# MainBoard.net
KiCad netlist of a schematic drawn in EAGLE
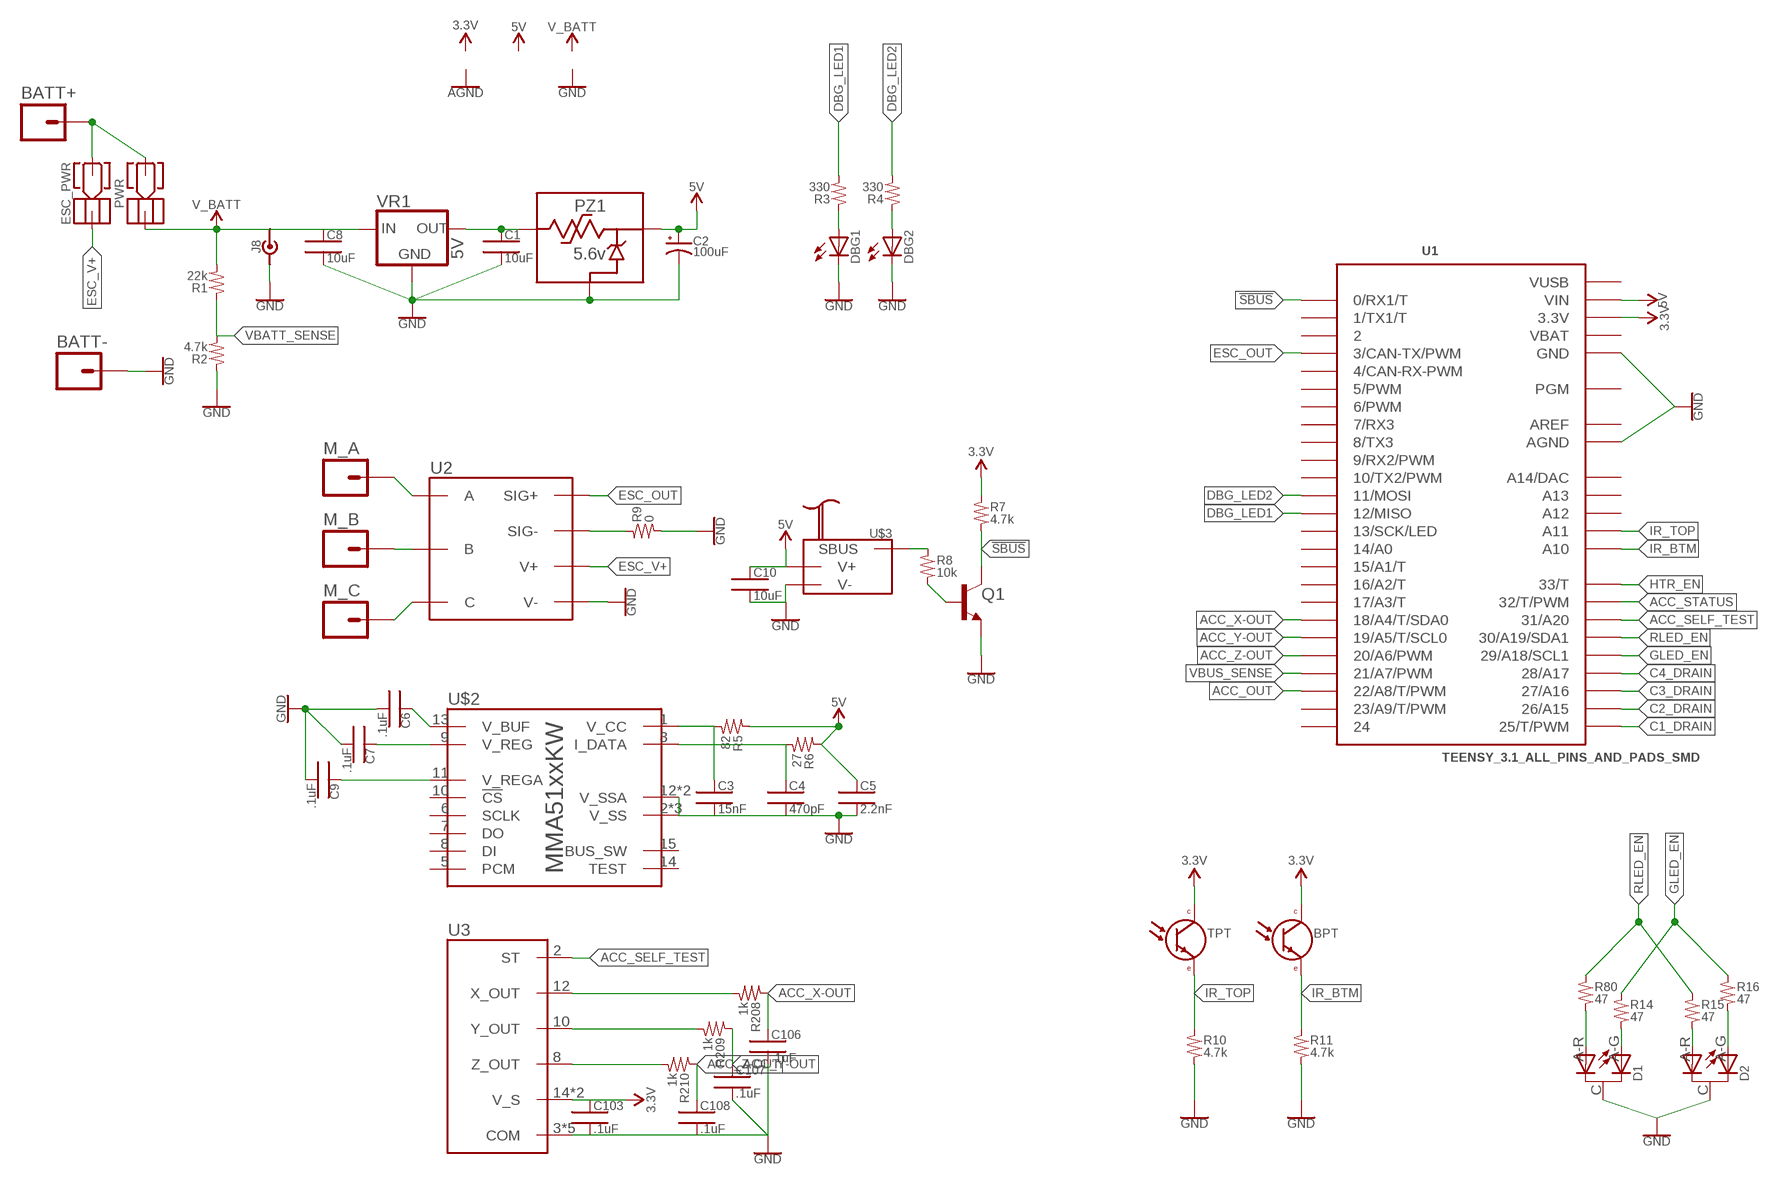
[diagram p0: schematic, sheet 1]

(export (version "E")
  (design (tool "Eeschema 10.0.6"))
  (components
    (comp (ref "BATT+")
      (value "14AWG_PTH")
      (footprint "eagle-import:14AWG_PTH")
      (libsource (lib "eagle-import") (part "14AWG_PTH"))
    )
    (comp (ref "BATT-")
      (value "14AWG_PTH")
      (footprint "eagle-import:14AWG_PTH")
      (libsource (lib "eagle-import") (part "14AWG_PTH"))
    )
    (comp (ref "BPT")
      (value "PHOTOTRANSISTOR_OPXXX-H")
      (footprint "eagle-import:OP550+_HORIZ")
      (libsource (lib "eagle-import") (part "PHOTOTRANSISTOR_OPXXX-H"))
    )
    (comp (ref "C1")
      (value "10uF")
      (footprint "eagle-import:0805")
      (libsource (lib "eagle-import") (part "CAP_SMD_0805"))
    )
    (comp (ref "C2")
      (value "100uF")
      (footprint "eagle-import:2917_D-CASE")
      (libsource (lib "eagle-import") (part "CAP_POL_SMD"))
    )
    (comp (ref "C3")
      (value "15nF")
      (footprint "eagle-import:0805")
      (libsource (lib "eagle-import") (part "CAP_SMD_0805"))
    )
    (comp (ref "C4")
      (value "470pF")
      (footprint "eagle-import:0805")
      (libsource (lib "eagle-import") (part "CAP_SMD_0805"))
    )
    (comp (ref "C5")
      (value "2.2nF")
      (footprint "eagle-import:0805")
      (libsource (lib "eagle-import") (part "CAP_SMD_0805"))
    )
    (comp (ref "C6")
      (value ".1uF")
      (footprint "eagle-import:0805")
      (libsource (lib "eagle-import") (part "CAP_SMD_0805"))
    )
    (comp (ref "C7")
      (value ".1uF")
      (footprint "eagle-import:0805")
      (libsource (lib "eagle-import") (part "CAP_SMD_0805"))
    )
    (comp (ref "C8")
      (value "10uF")
      (footprint "eagle-import:0805")
      (libsource (lib "eagle-import") (part "CAP_SMD_0805"))
    )
    (comp (ref "C9")
      (value ".1uF")
      (footprint "eagle-import:0805")
      (libsource (lib "eagle-import") (part "CAP_SMD_0805"))
    )
    (comp (ref "C10")
      (value "10uF")
      (footprint "eagle-import:0805")
      (libsource (lib "eagle-import") (part "CAP_SMD_0805"))
    )
    (comp (ref "C103")
      (value ".1uF")
      (footprint "eagle-import:0805")
      (libsource (lib "eagle-import") (part "CAP_SMD_0805"))
    )
    (comp (ref "C106")
      (value ".1uF")
      (footprint "eagle-import:0805")
      (libsource (lib "eagle-import") (part "CAP_SMD_0805"))
    )
    (comp (ref "C107")
      (value ".1uF")
      (footprint "eagle-import:0805")
      (libsource (lib "eagle-import") (part "CAP_SMD_0805"))
    )
    (comp (ref "C108")
      (value ".1uF")
      (footprint "eagle-import:0805")
      (libsource (lib "eagle-import") (part "CAP_SMD_0805"))
    )
    (comp (ref "D1")
      (value "TLVS5100")
      (footprint "eagle-import:TLSV5100")
      (libsource (lib "eagle-import") (part "TLVS5100"))
    )
    (comp (ref "D2")
      (value "TLVS5100")
      (footprint "eagle-import:TLSV5100")
      (libsource (lib "eagle-import") (part "TLVS5100"))
    )
    (comp (ref "DBG1")
      (value "LED1206")
      (footprint "eagle-import:LED-1206")
      (libsource (lib "eagle-import") (part "LED1206"))
    )
    (comp (ref "DBG2")
      (value "LED1206")
      (footprint "eagle-import:LED-1206")
      (libsource (lib "eagle-import") (part "LED1206"))
    )
    (comp (ref "ESC_PWR")
      (value "SCREW_SW_M3")
      (footprint "eagle-import:SCREW_SW_M3")
      (libsource (lib "eagle-import") (part "SCREW_SW_M3"))
    )
    (comp (ref "J8")
      (value "PJ-082BH")
      (footprint "eagle-import:PJ-082BH")
      (libsource (lib "eagle-import") (part "PJ-082BH"))
    )
    (comp (ref "M_A")
      (value "14AWG_PTH")
      (footprint "eagle-import:14AWG_PTH")
      (libsource (lib "eagle-import") (part "14AWG_PTH"))
    )
    (comp (ref "M_B")
      (value "14AWG_PTH")
      (footprint "eagle-import:14AWG_PTH")
      (libsource (lib "eagle-import") (part "14AWG_PTH"))
    )
    (comp (ref "M_C")
      (value "14AWG_PTH")
      (footprint "eagle-import:14AWG_PTH")
      (libsource (lib "eagle-import") (part "14AWG_PTH"))
    )
    (comp (ref "PWR")
      (value "SCREW_SW_M3")
      (footprint "eagle-import:SCREW_SW_M3")
      (libsource (lib "eagle-import") (part "SCREW_SW_M3"))
    )
    (comp (ref "PZ1")
      (value "5.6v")
      (footprint "eagle-import:POLYZEN_LS")
      (libsource (lib "eagle-import") (part "POLYZEN_LS"))
    )
    (comp (ref "Q1")
      (value "BJT_NPN")
      (footprint "eagle-import:SOT23-3")
      (libsource (lib "eagle-import") (part "BJT_NPN"))
    )
    (comp (ref "R1")
      (value "22k")
      (footprint "eagle-import:0805")
      (libsource (lib "eagle-import") (part "RES_SMD0805"))
    )
    (comp (ref "R2")
      (value "4.7k")
      (footprint "eagle-import:0805")
      (libsource (lib "eagle-import") (part "RES_SMD0805"))
    )
    (comp (ref "R3")
      (value "330")
      (footprint "eagle-import:0805")
      (libsource (lib "eagle-import") (part "RES_SMD0805"))
    )
    (comp (ref "R4")
      (value "330")
      (footprint "eagle-import:0805")
      (libsource (lib "eagle-import") (part "RES_SMD0805"))
    )
    (comp (ref "R5")
      (value "82")
      (footprint "eagle-import:0805")
      (libsource (lib "eagle-import") (part "RES_SMD0805"))
    )
    (comp (ref "R6")
      (value "27")
      (footprint "eagle-import:0805")
      (libsource (lib "eagle-import") (part "RES_SMD0805"))
    )
    (comp (ref "R7")
      (value "4.7k")
      (footprint "eagle-import:0805")
      (libsource (lib "eagle-import") (part "RES_SMD0805"))
    )
    (comp (ref "R8")
      (value "10k")
      (footprint "eagle-import:0805")
      (libsource (lib "eagle-import") (part "RES_SMD0805"))
    )
    (comp (ref "R9")
      (value "0")
      (footprint "eagle-import:0805")
      (libsource (lib "eagle-import") (part "RES_SMD0805"))
    )
    (comp (ref "R10")
      (value "4.7k")
      (footprint "eagle-import:0805")
      (libsource (lib "eagle-import") (part "RES_SMD0805"))
    )
    (comp (ref "R11")
      (value "4.7k")
      (footprint "eagle-import:0805")
      (libsource (lib "eagle-import") (part "RES_SMD0805"))
    )
    (comp (ref "R14")
      (value "47")
      (footprint "eagle-import:0805")
      (libsource (lib "eagle-import") (part "RES_SMD0805"))
    )
    (comp (ref "R15")
      (value "47")
      (footprint "eagle-import:0805")
      (libsource (lib "eagle-import") (part "RES_SMD0805"))
    )
    (comp (ref "R16")
      (value "47")
      (footprint "eagle-import:0805")
      (libsource (lib "eagle-import") (part "RES_SMD0805"))
    )
    (comp (ref "R80")
      (value "47")
      (footprint "eagle-import:0805")
      (libsource (lib "eagle-import") (part "RES_SMD0805"))
    )
    (comp (ref "R208")
      (value "1k")
      (footprint "eagle-import:0805")
      (libsource (lib "eagle-import") (part "RES_SMD0805"))
    )
    (comp (ref "R209")
      (value "1k")
      (footprint "eagle-import:0805")
      (libsource (lib "eagle-import") (part "RES_SMD0805"))
    )
    (comp (ref "R210")
      (value "1k")
      (footprint "eagle-import:0805")
      (libsource (lib "eagle-import") (part "RES_SMD0805"))
    )
    (comp (ref "TPT")
      (value "PHOTOTRANSISTOR_OPXXX-H")
      (footprint "eagle-import:OP550+_HORIZ")
      (libsource (lib "eagle-import") (part "PHOTOTRANSISTOR_OPXXX-H"))
    )
    (comp (ref "U$2")
      (value "MMA51XXKW")
      (footprint "eagle-import:QFN16")
      (libsource (lib "eagle-import") (part "MMA51XXKW"))
    )
    (comp (ref "U$3")
      (value "SBUS_RC_RX_FRSKY-XMPM")
      (footprint "eagle-import:FRSKY_XM_PLUS_MINI")
      (libsource (lib "eagle-import") (part "SBUS_RC_RX_FRSKY-XMPM"))
    )
    (comp (ref "U1")
      (value "TEENSY_3.1_ALL_PINS_AND_PADS_SMD")
      (footprint "eagle-import:TEENSY_3.1_SMD_ALLPINS")
      (libsource (lib "eagle-import") (part "TEENSY_3.1_ALL_PINS_AND_PADS_SMD"))
    )
    (comp (ref "U2")
      (value "ZTW_30A_BLDCESC")
      (footprint "eagle-import:ZTW_SPIDER_30A_HV_OPTO_ESC")
      (libsource (lib "eagle-import") (part "ZTW_30A_BLDCESC"))
    )
    (comp (ref "U3")
      (value "ADXL326_QFN16")
      (footprint "eagle-import:QFN16")
      (libsource (lib "eagle-import") (part "ADXL326_QFN16"))
    )
    (comp (ref "VR1")
      (value "5V")
      (footprint "eagle-import:TSR_2-XXXX")
      (libsource (lib "eagle-import") (part "TSR_2-XXXX"))
    )
  )
  (nets
    (net (code "1") (name "/AREF") (class "Default")
      (node (ref "U1") (pin "AREF") (pinfunction "AREF_AREF") (pintype "power_in"))
    )
    (net (code "2") (name "/VBAT") (class "Default")
      (node (ref "U1") (pin "VBAT") (pinfunction "VBAT_VBAT") (pintype "power_in"))
    )
    (net (code "3") (name "/VUSB") (class "Default")
      (node (ref "U1") (pin "VUSB") (pinfunction "VUSB_VUSB") (pintype "power_in"))
    )
    (net (code "4") (name "/~{SBUS}") (class "Default")
      (node (ref "Q1") (pin "3") (pinfunction "C_3") (pintype "passive"))
      (node (ref "R7") (pin "2") (pinfunction "2_2") (pintype "passive"))
      (node (ref "U1") (pin "0") (pinfunction "0/RX1/T_0") (pintype "bidirectional"))
    )
    (net (code "5") (name "3.3V") (class "Default")
      (node (ref "BPT") (pin "C") (pinfunction "C_C") (pintype "bidirectional"))
      (node (ref "C103") (pin "1") (pinfunction "1_1") (pintype "passive"))
      (node (ref "R7") (pin "1") (pinfunction "1_1") (pintype "passive"))
      (node (ref "TPT") (pin "C") (pinfunction "C_C") (pintype "bidirectional"))
      (node (ref "U1") (pin "3.3V") (pinfunction "3.3V_3.3V") (pintype "power_in"))
      (node (ref "U1") (pin "3.3V1") (pinfunction "3.3V_3.3V1") (pintype "power_in"))
      (node (ref "U1") (pin "3.3V2") (pinfunction "3.3V_3.3V2") (pintype "power_in"))
      (node (ref "U3") (pin "14") (pinfunction "V_S_14") (pintype "bidirectional"))
      (node (ref "U3") (pin "15") (pinfunction "V_S_15") (pintype "bidirectional"))
    )
    (net (code "6") (name "5V") (class "Default")
      (node (ref "C10") (pin "1") (pinfunction "1_1") (pintype "passive"))
      (node (ref "C2") (pin "A+") (pinfunction "+_A+") (pintype "passive"))
      (node (ref "C5") (pin "1") (pinfunction "1_1") (pintype "passive"))
      (node (ref "PZ1") (pin "VOUT") (pinfunction "V_OUT_VOUT") (pintype "bidirectional"))
      (node (ref "R5") (pin "1") (pinfunction "1_1") (pintype "passive"))
      (node (ref "R6") (pin "1") (pinfunction "1_1") (pintype "passive"))
      (node (ref "U$3") (pin "5V") (pinfunction "V+_5V") (pintype "bidirectional"))
      (node (ref "U1") (pin "VIN") (pinfunction "VIN_VIN") (pintype "power_in"))
    )
    (net (code "7") (name "ACC_OUT") (class "Default")
      (node (ref "U1") (pin "22/A8") (pinfunction "22/A8/T/PWM_22/A8") (pintype "bidirectional"))
    )
    (net (code "8") (name "ACC_SELF_TEST") (class "Default")
      (node (ref "U1") (pin "31") (pinfunction "31/A20_31") (pintype "bidirectional"))
      (node (ref "U3") (pin "2") (pinfunction "ST_2") (pintype "bidirectional"))
    )
    (net (code "9") (name "ACC_STATUS") (class "Default")
      (node (ref "U1") (pin "32") (pinfunction "32/T/PWM_32") (pintype "bidirectional"))
    )
    (net (code "10") (name "ACC_X-OUT") (class "Default")
      (node (ref "C106") (pin "1") (pinfunction "1_1") (pintype "passive"))
      (node (ref "R208") (pin "1") (pinfunction "1_1") (pintype "passive"))
      (node (ref "U1") (pin "18/A4") (pinfunction "18/A4/T/SDA0_18/A4") (pintype "bidirectional"))
    )
    (net (code "11") (name "ACC_Y-OUT") (class "Default")
      (node (ref "C107") (pin "1") (pinfunction "1_1") (pintype "passive"))
      (node (ref "R209") (pin "1") (pinfunction "1_1") (pintype "passive"))
      (node (ref "U1") (pin "19/A5") (pinfunction "19/A5/T/SCL0_19/A5") (pintype "bidirectional"))
    )
    (net (code "12") (name "ACC_Z-OUT") (class "Default")
      (node (ref "C108") (pin "1") (pinfunction "1_1") (pintype "passive"))
      (node (ref "R210") (pin "1") (pinfunction "1_1") (pintype "passive"))
      (node (ref "U1") (pin "20/A6") (pinfunction "20/A6/PWM_20/A6") (pintype "bidirectional"))
    )
    (net (code "14") (name "C1_DRAIN") (class "Default")
      (node (ref "U1") (pin "25") (pinfunction "25/T/PWM_25") (pintype "bidirectional"))
    )
    (net (code "15") (name "C2_DRAIN") (class "Default")
      (node (ref "U1") (pin "26") (pinfunction "26/A15_26") (pintype "bidirectional"))
    )
    (net (code "16") (name "C3_DRAIN") (class "Default")
      (node (ref "U1") (pin "27") (pinfunction "27/A16_27") (pintype "bidirectional"))
    )
    (net (code "17") (name "C4_DRAIN") (class "Default")
      (node (ref "U1") (pin "28") (pinfunction "28/A17_28") (pintype "bidirectional"))
    )
    (net (code "18") (name "DBG_LED1") (class "Default")
      (node (ref "R3") (pin "2") (pinfunction "2_2") (pintype "passive"))
      (node (ref "U1") (pin "12") (pinfunction "12/MISO_12") (pintype "bidirectional"))
    )
    (net (code "19") (name "DBG_LED2") (class "Default")
      (node (ref "R4") (pin "2") (pinfunction "2_2") (pintype "passive"))
      (node (ref "U1") (pin "11") (pinfunction "11/MOSI_11") (pintype "bidirectional"))
    )
    (net (code "20") (name "ESC_OUT") (class "Default")
      (node (ref "U1") (pin "3") (pinfunction "3/CAN-TX/PWM_3") (pintype "bidirectional"))
      (node (ref "U2") (pin "S+") (pinfunction "SIG+_S+") (pintype "bidirectional"))
    )
    (net (code "21") (name "ESC_V+") (class "Default")
      (node (ref "ESC_PWR") (pin "BLK") (pinfunction "BLK_BLK") (pintype "bidirectional"))
      (node (ref "U2") (pin "V0+") (pinfunction "V+_V0+") (pintype "bidirectional"))
      (node (ref "U2") (pin "V1+") (pinfunction "V+_V1+") (pintype "bidirectional"))
      (node (ref "U2") (pin "V2+") (pinfunction "V+_V2+") (pintype "bidirectional"))
      (node (ref "U2") (pin "V3+") (pinfunction "V+_V3+") (pintype "bidirectional"))
      (node (ref "U2") (pin "V4+") (pinfunction "V+_V4+") (pintype "bidirectional"))
    )
    (net (code "22") (name "GLED_EN") (class "Default")
      (node (ref "R14") (pin "1") (pinfunction "1_1") (pintype "passive"))
      (node (ref "R16") (pin "1") (pinfunction "1_1") (pintype "passive"))
      (node (ref "U1") (pin "29") (pinfunction "29/A18/SCL1_29") (pintype "bidirectional"))
    )
    (net (code "23") (name "GND") (class "Default")
      (node (ref "BATT-") (pin "P") (pinfunction "1_P") (pintype "passive"))
      (node (ref "C1") (pin "2") (pinfunction "2_2") (pintype "passive"))
      (node (ref "C10") (pin "2") (pinfunction "2_2") (pintype "passive"))
      (node (ref "C103") (pin "2") (pinfunction "2_2") (pintype "passive"))
      (node (ref "C106") (pin "2") (pinfunction "2_2") (pintype "passive"))
      (node (ref "C107") (pin "2") (pinfunction "2_2") (pintype "passive"))
      (node (ref "C108") (pin "2") (pinfunction "2_2") (pintype "passive"))
      (node (ref "C2") (pin "C-") (pinfunction "-_C-") (pintype "passive"))
      (node (ref "C3") (pin "2") (pinfunction "2_2") (pintype "passive"))
      (node (ref "C4") (pin "2") (pinfunction "2_2") (pintype "passive"))
      (node (ref "C5") (pin "2") (pinfunction "2_2") (pintype "passive"))
      (node (ref "C6") (pin "2") (pinfunction "2_2") (pintype "passive"))
      (node (ref "C7") (pin "2") (pinfunction "2_2") (pintype "passive"))
      (node (ref "C8") (pin "2") (pinfunction "2_2") (pintype "passive"))
      (node (ref "C9") (pin "2") (pinfunction "2_2") (pintype "passive"))
      (node (ref "D1") (pin "C") (pinfunction "C_C") (pintype "passive"))
      (node (ref "D2") (pin "C") (pinfunction "C_C") (pintype "passive"))
      (node (ref "DBG1") (pin "C") (pinfunction "C_C") (pintype "passive"))
      (node (ref "DBG2") (pin "C") (pinfunction "C_C") (pintype "passive"))
      (node (ref "J8") (pin "2") (pinfunction "2_2") (pintype "bidirectional"))
      (node (ref "J8") (pin "SH1") (pinfunction "2_SH1") (pintype "bidirectional"))
      (node (ref "J8") (pin "SH2") (pinfunction "2_SH2") (pintype "bidirectional"))
      (node (ref "J8") (pin "SH3") (pinfunction "2_SH3") (pintype "bidirectional"))
      (node (ref "J8") (pin "SH4") (pinfunction "2_SH4") (pintype "bidirectional"))
      (node (ref "PZ1") (pin "GND") (pinfunction "GND_GND") (pintype "bidirectional"))
      (node (ref "Q1") (pin "2") (pinfunction "E_2") (pintype "passive"))
      (node (ref "R10") (pin "2") (pinfunction "2_2") (pintype "passive"))
      (node (ref "R11") (pin "2") (pinfunction "2_2") (pintype "passive"))
      (node (ref "R2") (pin "1") (pinfunction "1_1") (pintype "passive"))
      (node (ref "R9") (pin "2") (pinfunction "2_2") (pintype "passive"))
      (node (ref "U$2") (pin "12") (pinfunction "V_SSA_12") (pintype "bidirectional"))
      (node (ref "U$2") (pin "16") (pinfunction "V_SSA_16") (pintype "bidirectional"))
      (node (ref "U$2") (pin "17") (pinfunction "V_SS_17") (pintype "bidirectional"))
      (node (ref "U$2") (pin "2") (pinfunction "V_SS_2") (pintype "bidirectional"))
      (node (ref "U$2") (pin "4") (pinfunction "V_SS_4") (pintype "bidirectional"))
      (node (ref "U$3") (pin "GND") (pinfunction "V-_GND") (pintype "bidirectional"))
      (node (ref "U1") (pin "AGND") (pinfunction "AGND_AGND") (pintype "power_in"))
      (node (ref "U1") (pin "GND") (pinfunction "GND_GND") (pintype "power_in"))
      (node (ref "U1") (pin "GND1") (pinfunction "GND_GND1") (pintype "power_in"))
      (node (ref "U1") (pin "GND2") (pinfunction "GND_GND2") (pintype "power_in"))
      (node (ref "U2") (pin "V0-") (pinfunction "V-_V0-") (pintype "bidirectional"))
      (node (ref "U2") (pin "V1-") (pinfunction "V-_V1-") (pintype "bidirectional"))
      (node (ref "U2") (pin "V2-") (pinfunction "V-_V2-") (pintype "bidirectional"))
      (node (ref "U2") (pin "V3-") (pinfunction "V-_V3-") (pintype "bidirectional"))
      (node (ref "U2") (pin "V4-") (pinfunction "V-_V4-") (pintype "bidirectional"))
      (node (ref "U3") (pin "17") (pinfunction "COM_17") (pintype "bidirectional"))
      (node (ref "U3") (pin "3") (pinfunction "COM_3") (pintype "bidirectional"))
      (node (ref "U3") (pin "5") (pinfunction "COM_5") (pintype "bidirectional"))
      (node (ref "U3") (pin "6") (pinfunction "COM_6") (pintype "bidirectional"))
      (node (ref "U3") (pin "7") (pinfunction "COM_7") (pintype "bidirectional"))
      (node (ref "VR1") (pin "2") (pinfunction "GND_2") (pintype "input"))
    )
    (net (code "24") (name "HTR_EN") (class "Default")
      (node (ref "U1") (pin "33") (pinfunction "33/T_33") (pintype "bidirectional"))
    )
    (net (code "25") (name "IR_BTM") (class "Default")
      (node (ref "BPT") (pin "E") (pinfunction "E_E") (pintype "bidirectional"))
      (node (ref "R11") (pin "1") (pinfunction "1_1") (pintype "passive"))
      (node (ref "U1") (pin "A10") (pinfunction "A10_A10") (pintype "bidirectional"))
    )
    (net (code "26") (name "IR_TOP") (class "Default")
      (node (ref "R10") (pin "1") (pinfunction "1_1") (pintype "passive"))
      (node (ref "TPT") (pin "E") (pinfunction "E_E") (pintype "bidirectional"))
      (node (ref "U1") (pin "A11") (pinfunction "A11_A11") (pintype "bidirectional"))
    )
    (net (code "27") (name "Net-(BATT+-1)") (class "Default")
      (node (ref "BATT+") (pin "P") (pinfunction "1_P") (pintype "passive"))
      (node (ref "ESC_PWR") (pin "BLT") (pinfunction "BLT_BLT") (pintype "bidirectional"))
      (node (ref "PWR") (pin "BLT") (pinfunction "BLT_BLT") (pintype "bidirectional"))
    )
    (net (code "28") (name "Net-(D1-A1)") (class "Default")
      (node (ref "D1") (pin "A-R") (pinfunction "A1_A-R") (pintype "passive"))
      (node (ref "R80") (pin "2") (pinfunction "2_2") (pintype "passive"))
    )
    (net (code "29") (name "Net-(D1-A2)") (class "Default")
      (node (ref "D1") (pin "A-G") (pinfunction "A2_A-G") (pintype "passive"))
      (node (ref "R14") (pin "2") (pinfunction "2_2") (pintype "passive"))
    )
    (net (code "30") (name "Net-(D2-A1)") (class "Default")
      (node (ref "D2") (pin "A-R") (pinfunction "A1_A-R") (pintype "passive"))
      (node (ref "R15") (pin "2") (pinfunction "2_2") (pintype "passive"))
    )
    (net (code "31") (name "Net-(D2-A2)") (class "Default")
      (node (ref "D2") (pin "A-G") (pinfunction "A2_A-G") (pintype "passive"))
      (node (ref "R16") (pin "2") (pinfunction "2_2") (pintype "passive"))
    )
    (net (code "32") (name "Net-(DBG1-PadA)") (class "Default")
      (node (ref "DBG1") (pin "A") (pinfunction "A_A") (pintype "passive"))
      (node (ref "R3") (pin "1") (pinfunction "1_1") (pintype "passive"))
    )
    (net (code "33") (name "Net-(DBG2-PadA)") (class "Default")
      (node (ref "DBG2") (pin "A") (pinfunction "A_A") (pintype "passive"))
      (node (ref "R4") (pin "1") (pinfunction "1_1") (pintype "passive"))
    )
    (net (code "34") (name "Net-(M_A-1)") (class "Default")
      (node (ref "M_A") (pin "P") (pinfunction "1_P") (pintype "passive"))
      (node (ref "U2") (pin "A0") (pinfunction "A_A0") (pintype "bidirectional"))
      (node (ref "U2") (pin "A1") (pinfunction "A_A1") (pintype "bidirectional"))
      (node (ref "U2") (pin "A2") (pinfunction "A_A2") (pintype "bidirectional"))
      (node (ref "U2") (pin "A3") (pinfunction "A_A3") (pintype "bidirectional"))
      (node (ref "U2") (pin "A4") (pinfunction "A_A4") (pintype "bidirectional"))
    )
    (net (code "35") (name "Net-(M_B-1)") (class "Default")
      (node (ref "M_B") (pin "P") (pinfunction "1_P") (pintype "passive"))
      (node (ref "U2") (pin "B0") (pinfunction "B_B0") (pintype "bidirectional"))
      (node (ref "U2") (pin "B1") (pinfunction "B_B1") (pintype "bidirectional"))
      (node (ref "U2") (pin "B2") (pinfunction "B_B2") (pintype "bidirectional"))
      (node (ref "U2") (pin "B3") (pinfunction "B_B3") (pintype "bidirectional"))
      (node (ref "U2") (pin "B4") (pinfunction "B_B4") (pintype "bidirectional"))
    )
    (net (code "36") (name "Net-(M_C-1)") (class "Default")
      (node (ref "M_C") (pin "P") (pinfunction "1_P") (pintype "passive"))
      (node (ref "U2") (pin "C0") (pinfunction "C_C0") (pintype "bidirectional"))
      (node (ref "U2") (pin "C1") (pinfunction "C_C1") (pintype "bidirectional"))
      (node (ref "U2") (pin "C2") (pinfunction "C_C2") (pintype "bidirectional"))
      (node (ref "U2") (pin "C3") (pinfunction "C_C3") (pintype "bidirectional"))
      (node (ref "U2") (pin "C4") (pinfunction "C_C4") (pintype "bidirectional"))
    )
    (net (code "37") (name "Net-(PZ1-V_IN)") (class "Default")
      (node (ref "C1") (pin "1") (pinfunction "1_1") (pintype "passive"))
      (node (ref "PZ1") (pin "VIN") (pinfunction "V_IN_VIN") (pintype "bidirectional"))
      (node (ref "VR1") (pin "3") (pinfunction "OUT_3") (pintype "passive"))
    )
    (net (code "38") (name "Net-(Q1-B)") (class "Default")
      (node (ref "Q1") (pin "1") (pinfunction "B_1") (pintype "passive"))
      (node (ref "R8") (pin "2") (pinfunction "2_2") (pintype "passive"))
    )
    (net (code "39") (name "Net-(R8-Pad1)") (class "Default")
      (node (ref "R8") (pin "1") (pinfunction "1_1") (pintype "passive"))
      (node (ref "U$3") (pin "SBUS") (pinfunction "SBUS_SBUS") (pintype "bidirectional"))
    )
    (net (code "40") (name "Net-(U$2-I_DATA)") (class "Default")
      (node (ref "C4") (pin "1") (pinfunction "1_1") (pintype "passive"))
      (node (ref "R6") (pin "2") (pinfunction "2_2") (pintype "passive"))
      (node (ref "U$2") (pin "3") (pinfunction "I_DATA_3") (pintype "bidirectional"))
    )
    (net (code "41") (name "Net-(U$2-V_BUF)") (class "Default")
      (node (ref "C6") (pin "1") (pinfunction "1_1") (pintype "passive"))
      (node (ref "U$2") (pin "13") (pinfunction "V_BUF_13") (pintype "bidirectional"))
    )
    (net (code "42") (name "Net-(U$2-V_CC)") (class "Default")
      (node (ref "C3") (pin "1") (pinfunction "1_1") (pintype "passive"))
      (node (ref "R5") (pin "2") (pinfunction "2_2") (pintype "passive"))
      (node (ref "U$2") (pin "1") (pinfunction "V_CC_1") (pintype "bidirectional"))
    )
    (net (code "43") (name "Net-(U$2-V_REG)") (class "Default")
      (node (ref "C7") (pin "1") (pinfunction "1_1") (pintype "passive"))
      (node (ref "U$2") (pin "9") (pinfunction "V_REG_9") (pintype "bidirectional"))
    )
    (net (code "44") (name "Net-(U$2-V_REGA)") (class "Default")
      (node (ref "C9") (pin "1") (pinfunction "1_1") (pintype "passive"))
      (node (ref "U$2") (pin "11") (pinfunction "V_REGA_11") (pintype "bidirectional"))
    )
    (net (code "45") (name "Net-(U2-SIG-)") (class "Default")
      (node (ref "R9") (pin "1") (pinfunction "1_1") (pintype "passive"))
      (node (ref "U2") (pin "S-") (pinfunction "SIG-_S-") (pintype "bidirectional"))
    )
    (net (code "46") (name "Net-(U3-X_OUT)") (class "Default")
      (node (ref "R208") (pin "2") (pinfunction "2_2") (pintype "passive"))
      (node (ref "U3") (pin "12") (pinfunction "X_OUT_12") (pintype "bidirectional"))
    )
    (net (code "47") (name "Net-(U3-Y_OUT)") (class "Default")
      (node (ref "R209") (pin "2") (pinfunction "2_2") (pintype "passive"))
      (node (ref "U3") (pin "10") (pinfunction "Y_OUT_10") (pintype "bidirectional"))
    )
    (net (code "48") (name "Net-(U3-Z_OUT)") (class "Default")
      (node (ref "R210") (pin "2") (pinfunction "2_2") (pintype "passive"))
      (node (ref "U3") (pin "8") (pinfunction "Z_OUT_8") (pintype "bidirectional"))
    )
    (net (code "49") (name "RLED_EN") (class "Default")
      (node (ref "R15") (pin "1") (pinfunction "1_1") (pintype "passive"))
      (node (ref "R80") (pin "1") (pinfunction "1_1") (pintype "passive"))
      (node (ref "U1") (pin "30") (pinfunction "30/A19/SDA1_30") (pintype "bidirectional"))
    )
    (net (code "50") (name "VBATT_SENSE") (class "Default")
      (node (ref "R1") (pin "1") (pinfunction "1_1") (pintype "passive"))
      (node (ref "R2") (pin "2") (pinfunction "2_2") (pintype "passive"))
    )
    (net (code "51") (name "VBUS_SENSE") (class "Default")
      (node (ref "U1") (pin "21/A7") (pinfunction "21/A7/PWM_21/A7") (pintype "bidirectional"))
    )
    (net (code "52") (name "V_BATT") (class "Default")
      (node (ref "C8") (pin "1") (pinfunction "1_1") (pintype "passive"))
      (node (ref "J8") (pin "1") (pinfunction "1_1") (pintype "bidirectional"))
      (node (ref "PWR") (pin "BLK") (pinfunction "BLK_BLK") (pintype "bidirectional"))
      (node (ref "R1") (pin "2") (pinfunction "2_2") (pintype "passive"))
      (node (ref "VR1") (pin "1") (pinfunction "IN_1") (pintype "input"))
    )
    (net (code "53") (name "unconnected-(U$2-BUS_SW-Pad15)") (class "Default")
      (node (ref "U$2") (pin "15") (pinfunction "BUS_SW_15") (pintype "bidirectional"))
    )
    (net (code "54") (name "unconnected-(U$2-DI-Pad8)") (class "Default")
      (node (ref "U$2") (pin "8") (pinfunction "DI_8") (pintype "bidirectional"))
    )
    (net (code "55") (name "unconnected-(U$2-DO-Pad7)") (class "Default")
      (node (ref "U$2") (pin "7") (pinfunction "DO_7") (pintype "bidirectional"))
    )
    (net (code "56") (name "unconnected-(U$2-PCM-Pad5)") (class "Default")
      (node (ref "U$2") (pin "5") (pinfunction "PCM_5") (pintype "bidirectional"))
    )
    (net (code "57") (name "unconnected-(U$2-SCLK-Pad6)") (class "Default")
      (node (ref "U$2") (pin "6") (pinfunction "SCLK_6") (pintype "bidirectional"))
    )
    (net (code "58") (name "unconnected-(U$2-TEST-Pad14)") (class "Default")
      (node (ref "U$2") (pin "14") (pinfunction "TEST_14") (pintype "bidirectional"))
    )
    (net (code "59") (name "unconnected-(U$2-~{CS}-Pad10)") (class "Default")
      (node (ref "U$2") (pin "10") (pinfunction "~{CS}_10") (pintype "bidirectional"))
    )
    (net (code "60") (name "unconnected-(U1-1{slash}TX1{slash}T-Pad1)") (class "Default")
      (node (ref "U1") (pin "1") (pinfunction "1/TX1/T_1") (pintype "bidirectional"))
    )
    (net (code "61") (name "unconnected-(U1-4{slash}CAN-RX-PWM-Pad4)") (class "Default")
      (node (ref "U1") (pin "4") (pinfunction "4/CAN-RX-PWM_4") (pintype "bidirectional"))
    )
    (net (code "62") (name "unconnected-(U1-5{slash}PWM-Pad5)") (class "Default")
      (node (ref "U1") (pin "5") (pinfunction "5/PWM_5") (pintype "bidirectional"))
    )
    (net (code "63") (name "unconnected-(U1-6{slash}PWM-Pad6)") (class "Default")
      (node (ref "U1") (pin "6") (pinfunction "6/PWM_6") (pintype "bidirectional"))
    )
    (net (code "64") (name "unconnected-(U1-7{slash}RX3-Pad7)") (class "Default")
      (node (ref "U1") (pin "7") (pinfunction "7/RX3_7") (pintype "bidirectional"))
    )
    (net (code "65") (name "unconnected-(U1-8{slash}TX3-Pad8)") (class "Default")
      (node (ref "U1") (pin "8") (pinfunction "8/TX3_8") (pintype "bidirectional"))
    )
    (net (code "66") (name "unconnected-(U1-9{slash}RX2{slash}PWM-Pad9)") (class "Default")
      (node (ref "U1") (pin "9") (pinfunction "9/RX2/PWM_9") (pintype "bidirectional"))
    )
    (net (code "67") (name "unconnected-(U1-10{slash}TX2{slash}PWM-Pad10)") (class "Default")
      (node (ref "U1") (pin "10") (pinfunction "10/TX2/PWM_10") (pintype "bidirectional"))
    )
    (net (code "68") (name "unconnected-(U1-13{slash}SCK{slash}LED-Pad13)") (class "Default")
      (node (ref "U1") (pin "13") (pinfunction "13/SCK/LED_13") (pintype "bidirectional"))
    )
    (net (code "69") (name "unconnected-(U1-15{slash}A1{slash}T-Pad15{slash}A1)") (class "Default")
      (node (ref "U1") (pin "15/A1") (pinfunction "15/A1/T_15/A1") (pintype "bidirectional"))
    )
    (net (code "70") (name "unconnected-(U1-16{slash}A2{slash}T-Pad16{slash}A2)") (class "Default")
      (node (ref "U1") (pin "16/A2") (pinfunction "16/A2/T_16/A2") (pintype "bidirectional"))
    )
    (net (code "71") (name "unconnected-(U1-17{slash}A3{slash}T-Pad17{slash}A3)") (class "Default")
      (node (ref "U1") (pin "17/A3") (pinfunction "17/A3/T_17/A3") (pintype "bidirectional"))
    )
    (net (code "72") (name "unconnected-(U1-23{slash}A9{slash}T{slash}PWM-Pad23{slash}A9)") (class "Default")
      (node (ref "U1") (pin "23/A9") (pinfunction "23/A9/T/PWM_23/A9") (pintype "bidirectional"))
    )
    (net (code "73") (name "unconnected-(U1-A14{slash}DAC-PadA14)") (class "Default")
      (node (ref "U1") (pin "A14") (pinfunction "A14/DAC_A14") (pintype "bidirectional"))
    )
    (net (code "74") (name "unconnected-(U1-Pad2)") (class "Default")
      (node (ref "U1") (pin "2") (pinfunction "2_2") (pintype "bidirectional"))
    )
    (net (code "75") (name "unconnected-(U1-Pad14{slash}A0)") (class "Default")
      (node (ref "U1") (pin "14/A0") (pinfunction "14/A0_14/A0") (pintype "bidirectional"))
    )
    (net (code "76") (name "unconnected-(U1-Pad24)") (class "Default")
      (node (ref "U1") (pin "24") (pinfunction "24_24") (pintype "bidirectional"))
    )
    (net (code "77") (name "unconnected-(U1-PadA12)") (class "Default")
      (node (ref "U1") (pin "A12") (pinfunction "A12_A12") (pintype "bidirectional"))
    )
    (net (code "78") (name "unconnected-(U1-PadA13)") (class "Default")
      (node (ref "U1") (pin "A13") (pinfunction "A13_A13") (pintype "bidirectional"))
    )
    (net (code "79") (name "unconnected-(U1-PadPGM)") (class "Default")
      (node (ref "U1") (pin "PGM") (pinfunction "PGM_PGM") (pintype "bidirectional"))
    )
  )
)
